# CW340_USERIO_USB.net
KiCad netlist of a schematic drawn in Altium Designer
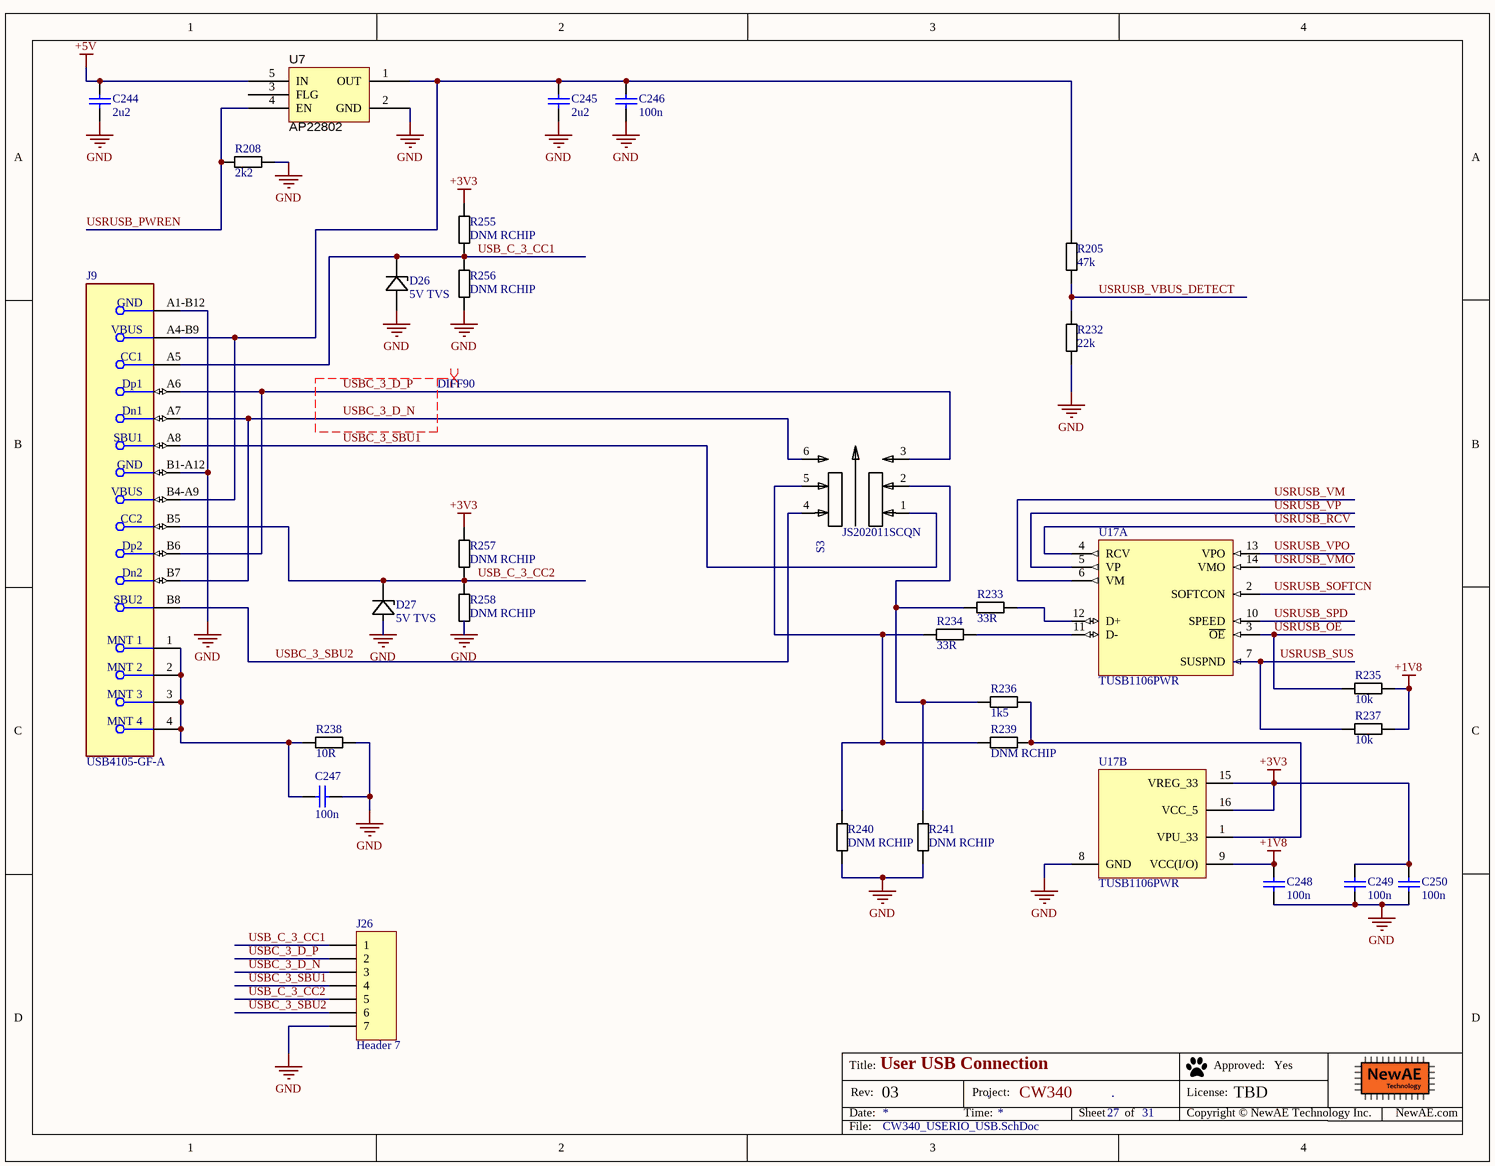
[diagram p0: CW340_USERIO_USB.SchDoc]

(export (version "E")
  (design (tool "Eeschema 10.0.6"))
  (components
    (comp (ref "C244")
      (value "2u2")
      (footprint "CAPC0603_M")
      (description "2u2, 0603")
      (fields (field (name "PART NUMBER") "CCHIP-2u2-0603"))
      (libsource (lib "NewAE_AltiumLib") (part "CAP"))
    )
    (comp (ref "C245")
      (value "2u2")
      (footprint "CAPC0603_M")
      (description "2u2, 0603")
      (fields (field (name "PART NUMBER") "CCHIP-2u2-0603"))
      (libsource (lib "NewAE_AltiumLib") (part "CAP"))
    )
    (comp (ref "C246")
      (value "100n")
      (footprint "CAPC0402_M")
      (description "100n, 0402")
      (fields (field (name "PART NUMBER") "CCHIP-100n-0402"))
      (libsource (lib "NewAE_AltiumLib") (part "CAP"))
    )
    (comp (ref "C247")
      (value "100n")
      (footprint "CAPC0603_M")
      (description "100n, 0603")
      (fields (field (name "PART NUMBER") "CCHIP-100n-0603"))
      (libsource (lib "NewAE_AltiumLib") (part "CAP"))
    )
    (comp (ref "C248")
      (value "100n")
      (footprint "CAPC0402_M")
      (description "100n, 0402")
      (fields (field (name "PART NUMBER") "CCHIP-100n-0402"))
      (libsource (lib "NewAE_AltiumLib") (part "CAP"))
    )
    (comp (ref "C249")
      (value "100n")
      (footprint "CAPC0402_M")
      (description "100n, 0402")
      (fields (field (name "PART NUMBER") "CCHIP-100n-0402"))
      (libsource (lib "NewAE_AltiumLib") (part "CAP"))
    )
    (comp (ref "C250")
      (value "100n")
      (footprint "CAPC0402_M")
      (description "100n, 0402")
      (fields (field (name "PART NUMBER") "CCHIP-100n-0402"))
      (libsource (lib "NewAE_AltiumLib") (part "CAP"))
    )
    (comp (ref "D26")
      (value "5V TVS")
      (footprint "SOD-523")
      (description "TVS DIODE 1VSO 5VBD SOD523")
      (fields (field (name "PART NUMBER") "VESD05B1-02V-G3-08"))
      (libsource (lib "NewAE_AltiumLib") (part "TVS_DIODE_CATHODE_PIN1"))
    )
    (comp (ref "D27")
      (value "5V TVS")
      (footprint "SOD-523")
      (description "TVS DIODE 1VSO 5VBD SOD523")
      (fields (field (name "PART NUMBER") "VESD05B1-02V-G3-08"))
      (libsource (lib "NewAE_AltiumLib") (part "TVS_DIODE_CATHODE_PIN1"))
    )
    (comp (ref "J9")
      (value "USB4105-GF-A")
      (footprint "FP-USB4105-GF-A-MFG")
      (description "CONN RCPT USB2.0 TYPEC 5A")
      (fields
        (field (name "MANUFACTURER") "GCT")
        (field (name "OCTOPART") "https://octopart.com/usb4105-gf-a-gct-106627878")
      )
      (libsource (lib "Altium Content Vault") (part "e7c17a616881a82b79941196b4bec10"))
    )
    (comp (ref "J26")
      (value "Header 7")
      (footprint "HDR1X7")
      (description "Header, 7-Pin")
      (fields (field (name "PUBLISHER") "Altium Limited"))
      (libsource (lib "Miscellaneous Connectors") (part "Header 7"))
    )
    (comp (ref "R205")
      (value "47k")
      (footprint "RESC1608X55N")
      (description "47k res, 0603, 1%, 1/10W")
      (fields (field (name "PART NUMBER") "RCHIP-47K-0603") (field (name "TOLERANCE") "1%"))
      (libsource (lib "") (part "RES-EU_1"))
    )
    (comp (ref "R208")
      (value "2k2")
      (footprint "RESC1005X40N")
      (description "2k2 res, 0402, 1%, 1/16W")
      (fields (field (name "PART NUMBER") "RCHIP-2K2-0402") (field (name "TOLERANCE") "1%"))
      (libsource (lib "NewAE_AltiumLib") (part "RES-EU"))
    )
    (comp (ref "R232")
      (value "22k")
      (footprint "RESC1608X55N")
      (description "22k res, 0603, 1%, 1/10W")
      (fields (field (name "PART NUMBER") "RCHIP-22K-0603") (field (name "TOLERANCE") "1%"))
      (libsource (lib "") (part "RES-EU_1"))
    )
    (comp (ref "R233")
      (value "33R")
      (footprint "RESC1608X55N")
      (description "33R res, 0603, 1%, 1/10W")
      (fields (field (name "PART NUMBER") "RCHIP-33R-0603") (field (name "TOLERANCE") "1%"))
      (libsource (lib "NewAE_AltiumLib") (part "RES-EU"))
    )
    (comp (ref "R234")
      (value "33R")
      (footprint "RESC1608X55N")
      (description "33R res, 0603, 1%, 1/10W")
      (fields (field (name "PART NUMBER") "RCHIP-33R-0603") (field (name "TOLERANCE") "1%"))
      (libsource (lib "NewAE_AltiumLib") (part "RES-EU"))
    )
    (comp (ref "R235")
      (value "10k")
      (footprint "RESC1005X40N")
      (description "10k res, 0402, 1%, 1/16W")
      (fields (field (name "PART NUMBER") "RCHIP-10K-0402") (field (name "TOLERANCE") "1%"))
      (libsource (lib "NewAE_AltiumLib") (part "RES-EU"))
    )
    (comp (ref "R236")
      (value "1k5")
      (footprint "RESC1608X55N")
      (description "1k5 res, 0603, 1%, 1/10W")
      (fields (field (name "PART NUMBER") "RCHIP-1K5-0603") (field (name "TOLERANCE") "1%"))
      (libsource (lib "NewAE_AltiumLib") (part "RES-EU"))
    )
    (comp (ref "R237")
      (value "10k")
      (footprint "RESC1005X40N")
      (description "10k res, 0402, 1%, 1/16W")
      (fields (field (name "PART NUMBER") "RCHIP-10K-0402") (field (name "TOLERANCE") "1%"))
      (libsource (lib "NewAE_AltiumLib") (part "RES-EU"))
    )
    (comp (ref "R238")
      (value "10R")
      (footprint "RESC1608X55N")
      (description "10R res, 0603, 1%, 1/10W")
      (fields (field (name "PART NUMBER") "RCHIP-10R-0603") (field (name "TOLERANCE") "1%"))
      (libsource (lib "NewAE_AltiumLib") (part "RES-EU"))
    )
    (comp (ref "R239")
      (value "DNM RCHIP")
      (footprint "RESC1608X55N")
      (description "Do Not Mount Resistor")
      (fields (field (name "PART NUMBER") "RCHIP-DNM-0603"))
      (libsource (lib "NewAE_AltiumLib") (part "RES-EU"))
    )
    (comp (ref "R240")
      (value "DNM RCHIP")
      (footprint "RESC1608X55N")
      (description "Do Not Mount Resistor")
      (fields (field (name "PART NUMBER") "RCHIP-DNM-0603"))
      (libsource (lib "") (part "RES-EU_2"))
    )
    (comp (ref "R241")
      (value "DNM RCHIP")
      (footprint "RESC1608X55N")
      (description "Do Not Mount Resistor")
      (fields (field (name "PART NUMBER") "RCHIP-DNM-0603"))
      (libsource (lib "") (part "RES-EU_2"))
    )
    (comp (ref "R255")
      (value "DNM RCHIP")
      (footprint "RESC1608X55N")
      (description "Do Not Mount Resistor")
      (fields (field (name "PART NUMBER") "RCHIP-DNM-0603"))
      (libsource (lib "") (part "RES-EU_1"))
    )
    (comp (ref "R256")
      (value "DNM RCHIP")
      (footprint "RESC1608X55N")
      (description "Do Not Mount Resistor")
      (fields (field (name "PART NUMBER") "RCHIP-DNM-0603"))
      (libsource (lib "") (part "RES-EU_1"))
    )
    (comp (ref "R257")
      (value "DNM RCHIP")
      (footprint "RESC1608X55N")
      (description "Do Not Mount Resistor")
      (fields (field (name "PART NUMBER") "RCHIP-DNM-0603"))
      (libsource (lib "") (part "RES-EU_1"))
    )
    (comp (ref "R258")
      (value "DNM RCHIP")
      (footprint "RESC1608X55N")
      (description "Do Not Mount Resistor")
      (fields (field (name "PART NUMBER") "RCHIP-DNM-0603"))
      (libsource (lib "") (part "RES-EU_1"))
    )
    (comp (ref "S3")
      (value "JS202011SCQN")
      (footprint "SW_JS202011SCQN")
      (description "DPDT SMD Switch, 300mA")
      (libsource (lib "NewAE_AltiumLib") (part "JS202011SCQN"))
    )
    (comp (ref "U7")
      (value "AP22802")
      (footprint "SOT23-5P95_285X145L45X40")
      (description "USB Power Switch, Digital IC")
      (fields (field (name "CREATED BY") "D.GODDARD"))
      (libsource (lib "NewAE_AltiumLib") (part "AP22802"))
    )
    (comp (ref "U17")
      (value "TUSB1106PWR")
      (footprint "PW0016A_L")
      (fields (field (name "MANUFACTURER") "Texas Instruments"))
      (libsource (lib "Altium Content Vault") (part "TI-TUSB1106-TSSOP_PW-16"))
    )
  )
  (nets
    (net (code "1") (name "+1V8") (class "Default")
      (node (ref "C248") (pin "1") (pinfunction "1_1") (pintype "passive"))
      (node (ref "R235") (pin "2") (pinfunction "2_2") (pintype "passive"))
      (node (ref "R237") (pin "2") (pinfunction "2_2") (pintype "passive"))
      (node (ref "U17") (pin "9") (pinfunction "VCC(I/O)_9") (pintype "power_in"))
    )
    (net (code "2") (name "+3V3") (class "Default")
      (node (ref "C249") (pin "1") (pinfunction "1_1") (pintype "passive"))
      (node (ref "C250") (pin "1") (pinfunction "1_1") (pintype "passive"))
      (node (ref "R255") (pin "1") (pinfunction "1_1") (pintype "passive"))
      (node (ref "R257") (pin "1") (pinfunction "1_1") (pintype "passive"))
      (node (ref "U17") (pin "15") (pinfunction "VREG_33_15") (pintype "power_in"))
      (node (ref "U17") (pin "16") (pinfunction "VCC_5_16") (pintype "power_in"))
    )
    (net (code "3") (name "+5V") (class "Default")
      (node (ref "C244") (pin "1") (pinfunction "1_1") (pintype "passive"))
      (node (ref "U7") (pin "5") (pinfunction "IN_5") (pintype "passive"))
    )
    (net (code "4") (name "/USBC_3_D_N") (class "Default")
      (node (ref "J26") (pin "3") (pinfunction "3_3") (pintype "passive"))
      (node (ref "J9") (pin "A7") (pinfunction "Dn1_A7") (pintype "bidirectional"))
      (node (ref "J9") (pin "B7") (pinfunction "Dn2_B7") (pintype "bidirectional"))
      (node (ref "S3") (pin "6") (pinfunction "6_6") (pintype "passive"))
    )
    (net (code "5") (name "/USBC_3_D_P") (class "Default")
      (node (ref "J26") (pin "2") (pinfunction "2_2") (pintype "passive"))
      (node (ref "J9") (pin "A6") (pinfunction "Dp1_A6") (pintype "bidirectional"))
      (node (ref "J9") (pin "B6") (pinfunction "Dp2_B6") (pintype "bidirectional"))
      (node (ref "S3") (pin "3") (pinfunction "3_3") (pintype "passive"))
    )
    (net (code "6") (name "/USBC_3_SBU1") (class "Default")
      (node (ref "J26") (pin "4") (pinfunction "4_4") (pintype "passive"))
      (node (ref "J9") (pin "A8") (pinfunction "SBU1_A8") (pintype "bidirectional"))
      (node (ref "S3") (pin "1") (pinfunction "1_1") (pintype "passive"))
    )
    (net (code "7") (name "/USBC_3_SBU2") (class "Default")
      (node (ref "J26") (pin "6") (pinfunction "6_6") (pintype "passive"))
      (node (ref "J9") (pin "B8") (pinfunction "SBU2_B8") (pintype "power_in"))
      (node (ref "S3") (pin "4") (pinfunction "4_4") (pintype "passive"))
    )
    (net (code "8") (name "/USB_C_3_CC1") (class "Default")
      (node (ref "D26") (pin "1") (pinfunction "K_1") (pintype "passive"))
      (node (ref "J26") (pin "1") (pinfunction "1_1") (pintype "passive"))
      (node (ref "J9") (pin "A5") (pinfunction "CC1_A5") (pintype "power_in"))
      (node (ref "R255") (pin "2") (pinfunction "2_2") (pintype "passive"))
      (node (ref "R256") (pin "1") (pinfunction "1_1") (pintype "passive"))
    )
    (net (code "9") (name "/USB_C_3_CC2") (class "Default")
      (node (ref "D27") (pin "1") (pinfunction "K_1") (pintype "passive"))
      (node (ref "J26") (pin "5") (pinfunction "5_5") (pintype "passive"))
      (node (ref "J9") (pin "B5") (pinfunction "CC2_B5") (pintype "bidirectional"))
      (node (ref "R257") (pin "2") (pinfunction "2_2") (pintype "passive"))
      (node (ref "R258") (pin "1") (pinfunction "1_1") (pintype "passive"))
    )
    (net (code "10") (name "/USRUSB_OE") (class "Default")
      (node (ref "R235") (pin "1") (pinfunction "1_1") (pintype "passive"))
      (node (ref "U17") (pin "3") (pinfunction "~{OE}_3") (pintype "input"))
    )
    (net (code "11") (name "/USRUSB_PWREN") (class "Default")
      (node (ref "R208") (pin "1") (pinfunction "1_1") (pintype "passive"))
      (node (ref "U7") (pin "4") (pinfunction "EN_4") (pintype "passive"))
    )
    (net (code "12") (name "/USRUSB_RCV") (class "Default")
      (node (ref "U17") (pin "4") (pinfunction "RCV_4") (pintype "output"))
    )
    (net (code "13") (name "/USRUSB_SOFTCN") (class "Default")
      (node (ref "U17") (pin "2") (pinfunction "SOFTCON_2") (pintype "input"))
    )
    (net (code "14") (name "/USRUSB_SPD") (class "Default")
      (node (ref "U17") (pin "10") (pinfunction "SPEED_10") (pintype "input"))
    )
    (net (code "15") (name "/USRUSB_SUS") (class "Default")
      (node (ref "R237") (pin "1") (pinfunction "1_1") (pintype "passive"))
      (node (ref "U17") (pin "7") (pinfunction "SUSPND_7") (pintype "input"))
    )
    (net (code "16") (name "/USRUSB_VBUS_DETECT") (class "Default")
      (node (ref "R205") (pin "2") (pinfunction "2_2") (pintype "passive"))
      (node (ref "R232") (pin "1") (pinfunction "1_1") (pintype "passive"))
    )
    (net (code "17") (name "/USRUSB_VM") (class "Default")
      (node (ref "U17") (pin "6") (pinfunction "VM_6") (pintype "output"))
    )
    (net (code "18") (name "/USRUSB_VMO") (class "Default")
      (node (ref "U17") (pin "14") (pinfunction "VMO_14") (pintype "input"))
    )
    (net (code "19") (name "/USRUSB_VP") (class "Default")
      (node (ref "U17") (pin "5") (pinfunction "VP_5") (pintype "output"))
    )
    (net (code "20") (name "/USRUSB_VPO") (class "Default")
      (node (ref "U17") (pin "13") (pinfunction "VPO_13") (pintype "input"))
    )
    (net (code "21") (name "GND") (class "Default")
      (node (ref "C244") (pin "2") (pinfunction "2_2") (pintype "passive"))
      (node (ref "C245") (pin "2") (pinfunction "2_2") (pintype "passive"))
      (node (ref "C246") (pin "2") (pinfunction "2_2") (pintype "passive"))
      (node (ref "C247") (pin "2") (pinfunction "2_2") (pintype "passive"))
      (node (ref "C248") (pin "2") (pinfunction "2_2") (pintype "passive"))
      (node (ref "C249") (pin "2") (pinfunction "2_2") (pintype "passive"))
      (node (ref "C250") (pin "2") (pinfunction "2_2") (pintype "passive"))
      (node (ref "D26") (pin "2") (pinfunction "A_2") (pintype "passive"))
      (node (ref "D27") (pin "2") (pinfunction "A_2") (pintype "passive"))
      (node (ref "J26") (pin "7") (pinfunction "7_7") (pintype "passive"))
      (node (ref "J9") (pin "A1-B12") (pinfunction "GND_A1-B12") (pintype "power_in"))
      (node (ref "J9") (pin "B1-A12") (pinfunction "GND_B1-A12") (pintype "bidirectional"))
      (node (ref "R208") (pin "2") (pinfunction "2_2") (pintype "passive"))
      (node (ref "R232") (pin "2") (pinfunction "2_2") (pintype "passive"))
      (node (ref "R238") (pin "2") (pinfunction "2_2") (pintype "passive"))
      (node (ref "R240") (pin "1") (pinfunction "1_1") (pintype "passive"))
      (node (ref "R241") (pin "1") (pinfunction "1_1") (pintype "passive"))
      (node (ref "R256") (pin "2") (pinfunction "2_2") (pintype "passive"))
      (node (ref "R258") (pin "2") (pinfunction "2_2") (pintype "passive"))
      (node (ref "U17") (pin "8") (pinfunction "GND_8") (pintype "power_in"))
      (node (ref "U7") (pin "2") (pinfunction "GND_2") (pintype "passive"))
    )
    (net (code "22") (name "Net-(J9-MNT_1)") (class "Default")
      (node (ref "C247") (pin "1") (pinfunction "1_1") (pintype "passive"))
      (node (ref "J9") (pin "1") (pinfunction "MNT_1_1") (pintype "power_in"))
      (node (ref "J9") (pin "2") (pinfunction "MNT_2_2") (pintype "power_in"))
      (node (ref "J9") (pin "3") (pinfunction "MNT_3_3") (pintype "power_in"))
      (node (ref "J9") (pin "4") (pinfunction "MNT_4_4") (pintype "power_in"))
      (node (ref "R238") (pin "1") (pinfunction "1_1") (pintype "passive"))
    )
    (net (code "23") (name "Net-(R233-Pad1)") (class "Default")
      (node (ref "R233") (pin "1") (pinfunction "1_1") (pintype "passive"))
      (node (ref "R236") (pin "1") (pinfunction "1_1") (pintype "passive"))
      (node (ref "R241") (pin "2") (pinfunction "2_2") (pintype "passive"))
      (node (ref "S3") (pin "2") (pinfunction "2_2") (pintype "passive"))
    )
    (net (code "24") (name "Net-(R234-Pad1)") (class "Default")
      (node (ref "R234") (pin "1") (pinfunction "1_1") (pintype "passive"))
      (node (ref "R239") (pin "1") (pinfunction "1_1") (pintype "passive"))
      (node (ref "R240") (pin "2") (pinfunction "2_2") (pintype "passive"))
      (node (ref "S3") (pin "5") (pinfunction "5_5") (pintype "passive"))
    )
    (net (code "25") (name "Net-(U7-OUT)") (class "Default")
      (node (ref "C245") (pin "1") (pinfunction "1_1") (pintype "passive"))
      (node (ref "C246") (pin "1") (pinfunction "1_1") (pintype "passive"))
      (node (ref "J9") (pin "A4-B9") (pinfunction "VBUS_A4-B9") (pintype "power_in"))
      (node (ref "J9") (pin "B4-A9") (pinfunction "VBUS_B4-A9") (pintype "bidirectional"))
      (node (ref "R205") (pin "1") (pinfunction "1_1") (pintype "passive"))
      (node (ref "U7") (pin "1") (pinfunction "OUT_1") (pintype "passive"))
    )
    (net (code "26") (name "Net-(U17A-D+)") (class "Default")
      (node (ref "R233") (pin "2") (pinfunction "2_2") (pintype "passive"))
      (node (ref "U17") (pin "12") (pinfunction "D+_12") (pintype "bidirectional"))
    )
    (net (code "27") (name "Net-(U17A-D-)") (class "Default")
      (node (ref "R234") (pin "2") (pinfunction "2_2") (pintype "passive"))
      (node (ref "U17") (pin "11") (pinfunction "D-_11") (pintype "bidirectional"))
    )
    (net (code "28") (name "Net-(U17B-VPU_33)") (class "Default")
      (node (ref "R236") (pin "2") (pinfunction "2_2") (pintype "passive"))
      (node (ref "R239") (pin "2") (pinfunction "2_2") (pintype "passive"))
      (node (ref "U17") (pin "1") (pinfunction "VPU_33_1") (pintype "power_in"))
    )
    (net (code "29") (name "unconnected-(U7-FLG-Pad3)") (class "Default")
      (node (ref "U7") (pin "3") (pinfunction "FLG_3") (pintype "passive"))
    )
  )
)
